# MAGIsDebugger-JLink.net
KiCad netlist of a schematic drawn in Altium Designer
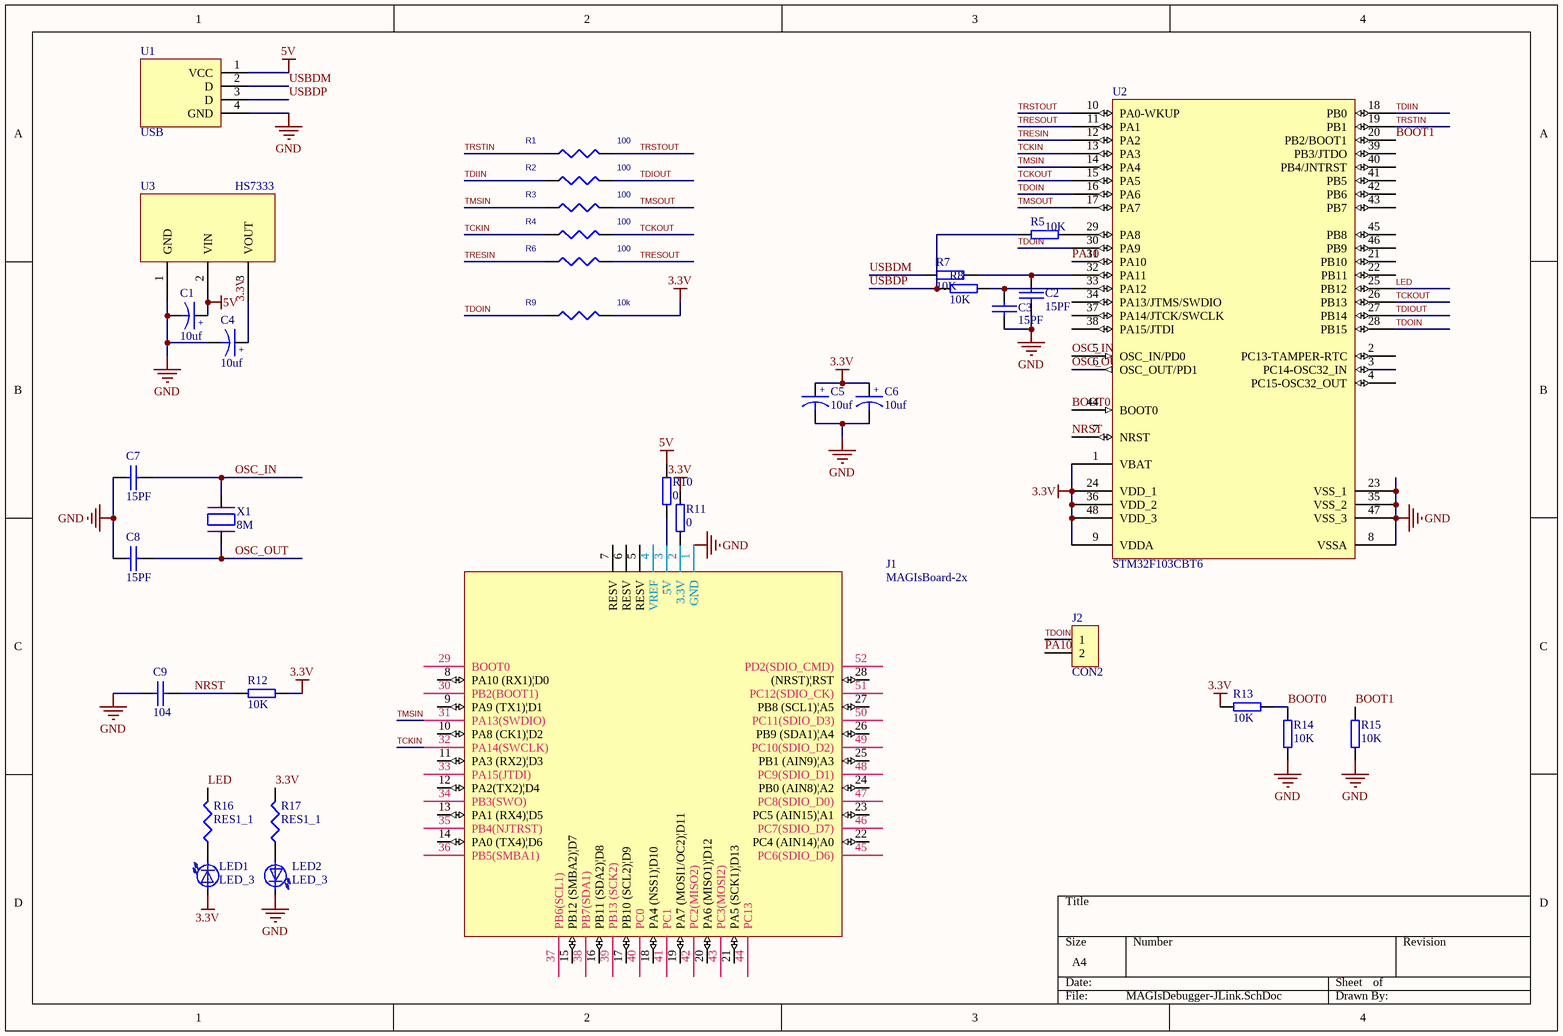
[diagram p0: MAGIsDebugger-JLink.SchDoc]

(export (version "E")
  (design (tool "Eeschema 10.0.6"))
  (components
    (comp (ref "C1")
      (value "10uf")
      (footprint "6-0805_n")
      (description "Capacitor")
      (libsource (lib "电容器") (part "CAPACITOR POL"))
    )
    (comp (ref "C2") (value "15PF") (footprint "6-0805_n") (libsource (lib "STM32") (part "CAP")))
    (comp (ref "C3") (value "15PF") (footprint "6-0805_n") (libsource (lib "STM32") (part "CAP")))
    (comp (ref "C4")
      (value "10uf")
      (footprint "6-0805_n")
      (description "Capacitor")
      (libsource (lib "电容器") (part "CAPACITOR POL"))
    )
    (comp (ref "C5")
      (value "10uf")
      (footprint "6-0805_n")
      (description "Capacitor")
      (libsource (lib "电容器") (part "CAPACITOR POL"))
    )
    (comp (ref "C6")
      (value "10uf")
      (footprint "6-0805_N")
      (description "Capacitor")
      (libsource (lib "电容器") (part "CAPACITOR POL"))
    )
    (comp (ref "C7") (value "15PF") (footprint "6-0805_n") (libsource (lib "STM32") (part "CAP")))
    (comp (ref "C8") (value "15PF") (footprint "6-0805_n") (libsource (lib "STM32") (part "CAP")))
    (comp (ref "C9") (value "104") (footprint "6-0805_n") (libsource (lib "STM32") (part "CAP")))
    (comp (ref "J1")
      (value "MAGIsBoard-2x")
      (footprint "MAGIsBoard-2x")
      (libsource (lib "MAGIsBoard") (part "MAGIsBoard-2x"))
    )
    (comp (ref "J2")
      (value "CON2")
      (footprint "SIP2")
      (description "Connector")
      (libsource (lib "CON系列") (part "CON2"))
    )
    (comp (ref "LED1") (value "LED_3") (footprint "6-0805_n") (libsource (lib "二极管") (part "LED_3")))
    (comp (ref "LED2") (value "LED_3") (footprint "6-0805_n") (libsource (lib "二极管") (part "LED_3")))
    (comp (ref "R1") (value "100") (libsource (lib "*") (part "RESISTOR/SM")))
    (comp (ref "R2") (value "100") (libsource (lib "*") (part "RESISTOR/SM")))
    (comp (ref "R3") (value "100") (libsource (lib "*") (part "RESISTOR/SM")))
    (comp (ref "R4") (value "100") (libsource (lib "*") (part "RESISTOR/SM")))
    (comp (ref "R5") (value "10K") (footprint "6-0805_n") (libsource (lib "STM32") (part "RES")))
    (comp (ref "R6") (value "100") (libsource (lib "*") (part "RESISTOR/SM")))
    (comp (ref "R7") (value "10K") (footprint "6-0805_n") (libsource (lib "STM32") (part "RES")))
    (comp (ref "R8") (value "10K") (footprint "6-0805_n") (libsource (lib "STM32") (part "RES")))
    (comp (ref "R9") (value "10k") (libsource (lib "*") (part "RESISTOR/SM")))
    (comp (ref "R10") (value "0") (footprint "6-0805_n") (libsource (lib "STM32") (part "RES")))
    (comp (ref "R11") (value "0") (footprint "6-0805_n") (libsource (lib "STM32") (part "RES")))
    (comp (ref "R12") (value "10K") (footprint "6-0805_n") (libsource (lib "STM32") (part "RES")))
    (comp (ref "R13") (value "10K") (footprint "6-0805_n") (libsource (lib "STM32") (part "RES")))
    (comp (ref "R14") (value "10K") (footprint "6-0805_n") (libsource (lib "STM32") (part "RES")))
    (comp (ref "R15") (value "10K") (footprint "6-0805_n") (libsource (lib "STM32") (part "RES")))
    (comp (ref "R16") (value "RES1_1") (footprint "6-0805_n") (libsource (lib "电阻器") (part "RES1_1")))
    (comp (ref "R17") (value "RES1_1") (footprint "6-0805_n") (libsource (lib "电阻器") (part "RES1_1")))
    (comp (ref "U1") (value "USB") (footprint "microUSB") (libsource (lib "USB接口") (part "USB")))
    (comp (ref "U2")
      (value "STM32F103CBT6")
      (footprint "LQFP48_N")
      (description "STM32 ARM-based 32-bit MCU with 128 Kbytes Flash, 48-pin LQFP, Industrial Temperature")
      (fields (field (name "PUBLISHER") "Altium Limited"))
      (libsource (lib "ST Microcontroller 32-Bit STM32") (part "STM32F103CBT6"))
    )
    (comp (ref "U3") (value "HS7333") (footprint "HS7333") (libsource (lib "PMIC") (part "HS7333")))
    (comp (ref "X1") (value "8M") (footprint "5032") (libsource (lib "STM32") (part "CRYSTAL")))
  )
  (nets
    (net (code "1") (name "/BOOT0") (class "Default")
      (node (ref "R13") (pin "1") (pinfunction "1_1") (pintype "passive"))
      (node (ref "R14") (pin "2") (pinfunction "2_2") (pintype "passive"))
      (node (ref "U2") (pin "44") (pinfunction "BOOT0_44") (pintype "input"))
    )
    (net (code "2") (name "/BOOT1") (class "Default")
      (node (ref "R15") (pin "2") (pinfunction "2_2") (pintype "passive"))
      (node (ref "U2") (pin "20") (pinfunction "PB2/BOOT1_20") (pintype "bidirectional"))
    )
    (net (code "3") (name "/LED") (class "Default")
      (node (ref "R16") (pin "2") (pinfunction "2_2") (pintype "passive"))
      (node (ref "U2") (pin "25") (pinfunction "PB12_25") (pintype "bidirectional"))
    )
    (net (code "4") (name "/NRST") (class "Default")
      (node (ref "C9") (pin "2") (pinfunction "2_2") (pintype "passive"))
      (node (ref "R12") (pin "1") (pinfunction "1_1") (pintype "passive"))
      (node (ref "U2") (pin "7") (pinfunction "NRST_7") (pintype "bidirectional"))
    )
    (net (code "5") (name "/OSC_IN") (class "Default")
      (node (ref "C7") (pin "2") (pinfunction "2_2") (pintype "passive"))
      (node (ref "U2") (pin "5") (pinfunction "OSC_IN/PD0_5") (pintype "input"))
      (node (ref "X1") (pin "1") (pinfunction "1_1") (pintype "passive"))
    )
    (net (code "6") (name "/OSC_OUT") (class "Default")
      (node (ref "C8") (pin "2") (pinfunction "2_2") (pintype "passive"))
      (node (ref "U2") (pin "6") (pinfunction "OSC_OUT/PD1_6") (pintype "output"))
      (node (ref "X1") (pin "2") (pinfunction "2_2") (pintype "passive"))
    )
    (net (code "7") (name "/PA10") (class "Default")
      (node (ref "J2") (pin "2") (pinfunction "2_2") (pintype "passive"))
      (node (ref "U2") (pin "31") (pinfunction "PA10_31") (pintype "bidirectional"))
    )
    (net (code "8") (name "/TCKIN") (class "Default")
      (node (ref "J1") (pin "32") (pinfunction "PA14(SWCLK)_32") (pintype "passive"))
      (node (ref "R4") (pin "1") (pinfunction "1_1") (pintype "passive"))
      (node (ref "U2") (pin "13") (pinfunction "PA3_13") (pintype "bidirectional"))
    )
    (net (code "9") (name "/TCKOUT") (class "Default")
      (node (ref "R4") (pin "2") (pinfunction "2_2") (pintype "passive"))
      (node (ref "U2") (pin "15") (pinfunction "PA5_15") (pintype "bidirectional"))
      (node (ref "U2") (pin "26") (pinfunction "PB13_26") (pintype "bidirectional"))
    )
    (net (code "10") (name "/TDIIN") (class "Default")
      (node (ref "R2") (pin "1") (pinfunction "1_1") (pintype "passive"))
      (node (ref "U2") (pin "18") (pinfunction "PB0_18") (pintype "bidirectional"))
    )
    (net (code "11") (name "/TDIOUT") (class "Default")
      (node (ref "R2") (pin "2") (pinfunction "2_2") (pintype "passive"))
      (node (ref "U2") (pin "27") (pinfunction "PB14_27") (pintype "bidirectional"))
    )
    (net (code "12") (name "/TDOIN") (class "Default")
      (node (ref "J2") (pin "1") (pinfunction "1_1") (pintype "passive"))
      (node (ref "R9") (pin "1") (pinfunction "1_1") (pintype "passive"))
      (node (ref "U2") (pin "16") (pinfunction "PA6_16") (pintype "bidirectional"))
      (node (ref "U2") (pin "28") (pinfunction "PB15_28") (pintype "bidirectional"))
      (node (ref "U2") (pin "30") (pinfunction "PA9_30") (pintype "bidirectional"))
    )
    (net (code "13") (name "/TMSIN") (class "Default")
      (node (ref "J1") (pin "31") (pinfunction "PA13(SWDIO)_31") (pintype "passive"))
      (node (ref "R3") (pin "1") (pinfunction "1_1") (pintype "passive"))
      (node (ref "U2") (pin "14") (pinfunction "PA4_14") (pintype "bidirectional"))
    )
    (net (code "14") (name "/TMSOUT") (class "Default")
      (node (ref "R3") (pin "2") (pinfunction "2_2") (pintype "passive"))
      (node (ref "U2") (pin "17") (pinfunction "PA7_17") (pintype "bidirectional"))
    )
    (net (code "15") (name "/TRESIN") (class "Default")
      (node (ref "R6") (pin "1") (pinfunction "1_1") (pintype "passive"))
      (node (ref "U2") (pin "12") (pinfunction "PA2_12") (pintype "bidirectional"))
    )
    (net (code "16") (name "/TRESOUT") (class "Default")
      (node (ref "R6") (pin "2") (pinfunction "2_2") (pintype "passive"))
      (node (ref "U2") (pin "11") (pinfunction "PA1_11") (pintype "bidirectional"))
    )
    (net (code "17") (name "/TRSTIN") (class "Default")
      (node (ref "R1") (pin "1") (pinfunction "1_1") (pintype "passive"))
      (node (ref "U2") (pin "19") (pinfunction "PB1_19") (pintype "bidirectional"))
    )
    (net (code "18") (name "/TRSTOUT") (class "Default")
      (node (ref "R1") (pin "2") (pinfunction "2_2") (pintype "passive"))
      (node (ref "U2") (pin "10") (pinfunction "PA0-WKUP_10") (pintype "bidirectional"))
    )
    (net (code "19") (name "/USBDM") (class "Default")
      (node (ref "R7") (pin "1") (pinfunction "1_1") (pintype "passive"))
      (node (ref "U1") (pin "2") (pinfunction "D_2") (pintype "passive"))
    )
    (net (code "20") (name "/USBDP") (class "Default")
      (node (ref "R5") (pin "1") (pinfunction "1_1") (pintype "passive"))
      (node (ref "R8") (pin "1") (pinfunction "1_1") (pintype "passive"))
      (node (ref "U1") (pin "3") (pinfunction "D_3") (pintype "passive"))
    )
    (net (code "21") (name "3.3V") (class "Default")
      (node (ref "C4") (pin "1") (pinfunction "1_1") (pintype "passive"))
      (node (ref "C5") (pin "1") (pinfunction "1_1") (pintype "passive"))
      (node (ref "C6") (pin "1") (pinfunction "1_1") (pintype "passive"))
      (node (ref "LED1") (pin "1") (pinfunction "A_1") (pintype "passive"))
      (node (ref "R11") (pin "1") (pinfunction "1_1") (pintype "passive"))
      (node (ref "R12") (pin "2") (pinfunction "2_2") (pintype "passive"))
      (node (ref "R13") (pin "2") (pinfunction "2_2") (pintype "passive"))
      (node (ref "R17") (pin "2") (pinfunction "2_2") (pintype "passive"))
      (node (ref "R9") (pin "2") (pinfunction "2_2") (pintype "passive"))
      (node (ref "U2") (pin "1") (pinfunction "VBAT_1") (pintype "power_in"))
      (node (ref "U2") (pin "24") (pinfunction "VDD_1_24") (pintype "power_in"))
      (node (ref "U2") (pin "36") (pinfunction "VDD_2_36") (pintype "power_in"))
      (node (ref "U2") (pin "48") (pinfunction "VDD_3_48") (pintype "power_in"))
      (node (ref "U2") (pin "9") (pinfunction "VDDA_9") (pintype "power_in"))
      (node (ref "U3") (pin "3") (pinfunction "VOUT_3") (pintype "passive"))
    )
    (net (code "22") (name "5V") (class "Default")
      (node (ref "C1") (pin "1") (pinfunction "1_1") (pintype "passive"))
      (node (ref "R10") (pin "1") (pinfunction "1_1") (pintype "passive"))
      (node (ref "U1") (pin "1") (pinfunction "VCC_1") (pintype "passive"))
      (node (ref "U3") (pin "2") (pinfunction "VIN_2") (pintype "passive"))
    )
    (net (code "23") (name "GND") (class "Default")
      (node (ref "C1") (pin "2") (pinfunction "2_2") (pintype "passive"))
      (node (ref "C2") (pin "1") (pinfunction "1_1") (pintype "passive"))
      (node (ref "C3") (pin "1") (pinfunction "1_1") (pintype "passive"))
      (node (ref "C4") (pin "2") (pinfunction "2_2") (pintype "passive"))
      (node (ref "C5") (pin "2") (pinfunction "2_2") (pintype "passive"))
      (node (ref "C6") (pin "2") (pinfunction "2_2") (pintype "passive"))
      (node (ref "C7") (pin "1") (pinfunction "1_1") (pintype "passive"))
      (node (ref "C8") (pin "1") (pinfunction "1_1") (pintype "passive"))
      (node (ref "C9") (pin "1") (pinfunction "1_1") (pintype "passive"))
      (node (ref "J1") (pin "1") (pinfunction "GND_1") (pintype "power_in"))
      (node (ref "LED2") (pin "2") (pinfunction "K_2") (pintype "passive"))
      (node (ref "R14") (pin "1") (pinfunction "1_1") (pintype "passive"))
      (node (ref "R15") (pin "1") (pinfunction "1_1") (pintype "passive"))
      (node (ref "U1") (pin "4") (pinfunction "GND_4") (pintype "passive"))
      (node (ref "U2") (pin "23") (pinfunction "VSS_1_23") (pintype "power_in"))
      (node (ref "U2") (pin "35") (pinfunction "VSS_2_35") (pintype "power_in"))
      (node (ref "U2") (pin "47") (pinfunction "VSS_3_47") (pintype "power_in"))
      (node (ref "U2") (pin "8") (pinfunction "VSSA_8") (pintype "power_in"))
      (node (ref "U3") (pin "1") (pinfunction "GND_1") (pintype "passive"))
    )
    (net (code "24") (name "Net-(J1-3.3V)") (class "Default")
      (node (ref "J1") (pin "2") (pinfunction "3.3V_2") (pintype "power_in"))
      (node (ref "R11") (pin "2") (pinfunction "2_2") (pintype "passive"))
    )
    (net (code "25") (name "Net-(J1-5V)") (class "Default")
      (node (ref "J1") (pin "3") (pinfunction "5V_3") (pintype "power_in"))
      (node (ref "R10") (pin "2") (pinfunction "2_2") (pintype "passive"))
    )
    (net (code "26") (name "Net-(LED1-K)") (class "Default")
      (node (ref "LED1") (pin "2") (pinfunction "K_2") (pintype "passive"))
      (node (ref "R16") (pin "1") (pinfunction "1_1") (pintype "passive"))
    )
    (net (code "27") (name "Net-(LED2-A)") (class "Default")
      (node (ref "LED2") (pin "1") (pinfunction "A_1") (pintype "passive"))
      (node (ref "R17") (pin "1") (pinfunction "1_1") (pintype "passive"))
    )
    (net (code "28") (name "Net-(U2-PA8)") (class "Default")
      (node (ref "R5") (pin "2") (pinfunction "2_2") (pintype "passive"))
      (node (ref "U2") (pin "29") (pinfunction "PA8_29") (pintype "bidirectional"))
    )
    (net (code "29") (name "Net-(U2-PA11)") (class "Default")
      (node (ref "C2") (pin "2") (pinfunction "2_2") (pintype "passive"))
      (node (ref "R7") (pin "2") (pinfunction "2_2") (pintype "passive"))
      (node (ref "U2") (pin "32") (pinfunction "PA11_32") (pintype "bidirectional"))
    )
    (net (code "30") (name "Net-(U2-PA12)") (class "Default")
      (node (ref "C3") (pin "2") (pinfunction "2_2") (pintype "passive"))
      (node (ref "R8") (pin "2") (pinfunction "2_2") (pintype "passive"))
      (node (ref "U2") (pin "33") (pinfunction "PA12_33") (pintype "bidirectional"))
    )
    (net (code "31") (name "unconnected-(J1-(NRST)¦RST-Pad28)") (class "Default")
      (node (ref "J1") (pin "28") (pinfunction "(NRST)¦RST_28") (pintype "bidirectional"))
    )
    (net (code "32") (name "unconnected-(J1-BOOT0-Pad29)") (class "Default")
      (node (ref "J1") (pin "29") (pinfunction "BOOT0_29") (pintype "passive"))
    )
    (net (code "33") (name "unconnected-(J1-PA0_(TX4)¦D6-Pad14)") (class "Default")
      (node (ref "J1") (pin "14") (pinfunction "PA0_(TX4)¦D6_14") (pintype "bidirectional"))
    )
    (net (code "34") (name "unconnected-(J1-PA1_(RX4)¦D5-Pad13)") (class "Default")
      (node (ref "J1") (pin "13") (pinfunction "PA1_(RX4)¦D5_13") (pintype "bidirectional"))
    )
    (net (code "35") (name "unconnected-(J1-PA2(TX2)¦D4-Pad12)") (class "Default")
      (node (ref "J1") (pin "12") (pinfunction "PA2(TX2)¦D4_12") (pintype "bidirectional"))
    )
    (net (code "36") (name "unconnected-(J1-PA3_(RX2)¦D3-Pad11)") (class "Default")
      (node (ref "J1") (pin "11") (pinfunction "PA3_(RX2)¦D3_11") (pintype "bidirectional"))
    )
    (net (code "37") (name "unconnected-(J1-PA4_(NSS1)¦D10-Pad18)") (class "Default")
      (node (ref "J1") (pin "18") (pinfunction "PA4_(NSS1)¦D10_18") (pintype "bidirectional"))
    )
    (net (code "38") (name "unconnected-(J1-PA5_(SCK1)¦D13-Pad21)") (class "Default")
      (node (ref "J1") (pin "21") (pinfunction "PA5_(SCK1)¦D13_21") (pintype "bidirectional"))
    )
    (net (code "39") (name "unconnected-(J1-PA6_(MISO1)¦D12-Pad20)") (class "Default")
      (node (ref "J1") (pin "20") (pinfunction "PA6_(MISO1)¦D12_20") (pintype "bidirectional"))
    )
    (net (code "40") (name "unconnected-(J1-PA7_(MOSI1{slash}OC2)¦D11-Pad19)") (class "Default")
      (node (ref "J1") (pin "19") (pinfunction "PA7_(MOSI1/OC2)¦D11_19") (pintype "bidirectional"))
    )
    (net (code "41") (name "unconnected-(J1-PA8_(CK1)¦D2-Pad10)") (class "Default")
      (node (ref "J1") (pin "10") (pinfunction "PA8_(CK1)¦D2_10") (pintype "bidirectional"))
    )
    (net (code "42") (name "unconnected-(J1-PA9_(TX1)¦D1-Pad9)") (class "Default")
      (node (ref "J1") (pin "9") (pinfunction "PA9_(TX1)¦D1_9") (pintype "bidirectional"))
    )
    (net (code "43") (name "unconnected-(J1-PA10_(RX1)¦D0-Pad8)") (class "Default")
      (node (ref "J1") (pin "8") (pinfunction "PA10_(RX1)¦D0_8") (pintype "bidirectional"))
    )
    (net (code "44") (name "unconnected-(J1-PA15(JTDI)-Pad33)") (class "Default")
      (node (ref "J1") (pin "33") (pinfunction "PA15(JTDI)_33") (pintype "passive"))
    )
    (net (code "45") (name "unconnected-(J1-PB0_(AIN8)¦A2-Pad24)") (class "Default")
      (node (ref "J1") (pin "24") (pinfunction "PB0_(AIN8)¦A2_24") (pintype "bidirectional"))
    )
    (net (code "46") (name "unconnected-(J1-PB1_(AIN9)¦A3-Pad25)") (class "Default")
      (node (ref "J1") (pin "25") (pinfunction "PB1_(AIN9)¦A3_25") (pintype "bidirectional"))
    )
    (net (code "47") (name "unconnected-(J1-PB2(BOOT1)-Pad30)") (class "Default")
      (node (ref "J1") (pin "30") (pinfunction "PB2(BOOT1)_30") (pintype "passive"))
    )
    (net (code "48") (name "unconnected-(J1-PB3(SWO)-Pad34)") (class "Default")
      (node (ref "J1") (pin "34") (pinfunction "PB3(SWO)_34") (pintype "passive"))
    )
    (net (code "49") (name "unconnected-(J1-PB4(NJTRST)-Pad35)") (class "Default")
      (node (ref "J1") (pin "35") (pinfunction "PB4(NJTRST)_35") (pintype "passive"))
    )
    (net (code "50") (name "unconnected-(J1-PB5(SMBA1)-Pad36)") (class "Default")
      (node (ref "J1") (pin "36") (pinfunction "PB5(SMBA1)_36") (pintype "passive"))
    )
    (net (code "51") (name "unconnected-(J1-PB6(SCL1)-Pad37)") (class "Default")
      (node (ref "J1") (pin "37") (pinfunction "PB6(SCL1)_37") (pintype "passive"))
    )
    (net (code "52") (name "unconnected-(J1-PB7(SDA1)-Pad38)") (class "Default")
      (node (ref "J1") (pin "38") (pinfunction "PB7(SDA1)_38") (pintype "passive"))
    )
    (net (code "53") (name "unconnected-(J1-PB8_(SCL1)¦A5-Pad27)") (class "Default")
      (node (ref "J1") (pin "27") (pinfunction "PB8_(SCL1)¦A5_27") (pintype "bidirectional"))
    )
    (net (code "54") (name "unconnected-(J1-PB9_(SDA1)¦A4-Pad26)") (class "Default")
      (node (ref "J1") (pin "26") (pinfunction "PB9_(SDA1)¦A4_26") (pintype "bidirectional"))
    )
    (net (code "55") (name "unconnected-(J1-PB10_(SCL2)¦D9-Pad17)") (class "Default")
      (node (ref "J1") (pin "17") (pinfunction "PB10_(SCL2)¦D9_17") (pintype "bidirectional"))
    )
    (net (code "56") (name "unconnected-(J1-PB11_(SDA2)¦D8-Pad16)") (class "Default")
      (node (ref "J1") (pin "16") (pinfunction "PB11_(SDA2)¦D8_16") (pintype "bidirectional"))
    )
    (net (code "57") (name "unconnected-(J1-PB12_(SMBA2)¦D7-Pad15)") (class "Default")
      (node (ref "J1") (pin "15") (pinfunction "PB12_(SMBA2)¦D7_15") (pintype "bidirectional"))
    )
    (net (code "58") (name "unconnected-(J1-PB13_(SCK2)-Pad39)") (class "Default")
      (node (ref "J1") (pin "39") (pinfunction "PB13_(SCK2)_39") (pintype "passive"))
    )
    (net (code "59") (name "unconnected-(J1-PC0-Pad40)") (class "Default")
      (node (ref "J1") (pin "40") (pinfunction "PC0_40") (pintype "passive"))
    )
    (net (code "60") (name "unconnected-(J1-PC1-Pad41)") (class "Default")
      (node (ref "J1") (pin "41") (pinfunction "PC1_41") (pintype "passive"))
    )
    (net (code "61") (name "unconnected-(J1-PC2(MISO2)-Pad42)") (class "Default")
      (node (ref "J1") (pin "42") (pinfunction "PC2(MISO2)_42") (pintype "passive"))
    )
    (net (code "62") (name "unconnected-(J1-PC3(MOSI2)-Pad43)") (class "Default")
      (node (ref "J1") (pin "43") (pinfunction "PC3(MOSI2)_43") (pintype "passive"))
    )
    (net (code "63") (name "unconnected-(J1-PC4_(AIN14)¦A0-Pad22)") (class "Default")
      (node (ref "J1") (pin "22") (pinfunction "PC4_(AIN14)¦A0_22") (pintype "bidirectional"))
    )
    (net (code "64") (name "unconnected-(J1-PC5_(AIN15)¦A1-Pad23)") (class "Default")
      (node (ref "J1") (pin "23") (pinfunction "PC5_(AIN15)¦A1_23") (pintype "bidirectional"))
    )
    (net (code "65") (name "unconnected-(J1-PC6(SDIO_D6)-Pad45)") (class "Default")
      (node (ref "J1") (pin "45") (pinfunction "PC6(SDIO_D6)_45") (pintype "passive"))
    )
    (net (code "66") (name "unconnected-(J1-PC7(SDIO_D7)-Pad46)") (class "Default")
      (node (ref "J1") (pin "46") (pinfunction "PC7(SDIO_D7)_46") (pintype "passive"))
    )
    (net (code "67") (name "unconnected-(J1-PC8(SDIO_D0)-Pad47)") (class "Default")
      (node (ref "J1") (pin "47") (pinfunction "PC8(SDIO_D0)_47") (pintype "passive"))
    )
    (net (code "68") (name "unconnected-(J1-PC9(SDIO_D1)-Pad48)") (class "Default")
      (node (ref "J1") (pin "48") (pinfunction "PC9(SDIO_D1)_48") (pintype "passive"))
    )
    (net (code "69") (name "unconnected-(J1-PC10(SDIO_D2)-Pad49)") (class "Default")
      (node (ref "J1") (pin "49") (pinfunction "PC10(SDIO_D2)_49") (pintype "passive"))
    )
    (net (code "70") (name "unconnected-(J1-PC11(SDIO_D3)-Pad50)") (class "Default")
      (node (ref "J1") (pin "50") (pinfunction "PC11(SDIO_D3)_50") (pintype "passive"))
    )
    (net (code "71") (name "unconnected-(J1-PC12(SDIO_CK)-Pad51)") (class "Default")
      (node (ref "J1") (pin "51") (pinfunction "PC12(SDIO_CK)_51") (pintype "passive"))
    )
    (net (code "72") (name "unconnected-(J1-PC13-Pad44)") (class "Default")
      (node (ref "J1") (pin "44") (pinfunction "PC13_44") (pintype "passive"))
    )
    (net (code "73") (name "unconnected-(J1-PD2(SDIO_CMD)-Pad52)") (class "Default")
      (node (ref "J1") (pin "52") (pinfunction "PD2(SDIO_CMD)_52") (pintype "passive"))
    )
    (net (code "74") (name "unconnected-(J1-RESV-Pad5)") (class "Default")
      (node (ref "J1") (pin "5") (pinfunction "RESV_5") (pintype "passive"))
    )
    (net (code "75") (name "unconnected-(J1-RESV-Pad6)") (class "Default")
      (node (ref "J1") (pin "6") (pinfunction "RESV_6") (pintype "passive"))
    )
    (net (code "76") (name "unconnected-(J1-RESV-Pad7)") (class "Default")
      (node (ref "J1") (pin "7") (pinfunction "RESV_7") (pintype "passive"))
    )
    (net (code "77") (name "unconnected-(J1-VREF-Pad4)") (class "Default")
      (node (ref "J1") (pin "4") (pinfunction "VREF_4") (pintype "passive"))
    )
    (net (code "78") (name "unconnected-(U2-PA13{slash}JTMS{slash}SWDIO-Pad34)") (class "Default")
      (node (ref "U2") (pin "34") (pinfunction "PA13/JTMS/SWDIO_34") (pintype "bidirectional"))
    )
    (net (code "79") (name "unconnected-(U2-PA14{slash}JTCK{slash}SWCLK-Pad37)") (class "Default")
      (node (ref "U2") (pin "37") (pinfunction "PA14/JTCK/SWCLK_37") (pintype "bidirectional"))
    )
    (net (code "80") (name "unconnected-(U2-PA15{slash}JTDI-Pad38)") (class "Default")
      (node (ref "U2") (pin "38") (pinfunction "PA15/JTDI_38") (pintype "bidirectional"))
    )
    (net (code "81") (name "unconnected-(U2-PB3{slash}JTDO-Pad39)") (class "Default")
      (node (ref "U2") (pin "39") (pinfunction "PB3/JTDO_39") (pintype "bidirectional"))
    )
    (net (code "82") (name "unconnected-(U2-PB4{slash}JNTRST-Pad40)") (class "Default")
      (node (ref "U2") (pin "40") (pinfunction "PB4/JNTRST_40") (pintype "bidirectional"))
    )
    (net (code "83") (name "unconnected-(U2-PB5-Pad41)") (class "Default")
      (node (ref "U2") (pin "41") (pinfunction "PB5_41") (pintype "bidirectional"))
    )
    (net (code "84") (name "unconnected-(U2-PB6-Pad42)") (class "Default")
      (node (ref "U2") (pin "42") (pinfunction "PB6_42") (pintype "bidirectional"))
    )
    (net (code "85") (name "unconnected-(U2-PB7-Pad43)") (class "Default")
      (node (ref "U2") (pin "43") (pinfunction "PB7_43") (pintype "bidirectional"))
    )
    (net (code "86") (name "unconnected-(U2-PB8-Pad45)") (class "Default")
      (node (ref "U2") (pin "45") (pinfunction "PB8_45") (pintype "bidirectional"))
    )
    (net (code "87") (name "unconnected-(U2-PB9-Pad46)") (class "Default")
      (node (ref "U2") (pin "46") (pinfunction "PB9_46") (pintype "bidirectional"))
    )
    (net (code "88") (name "unconnected-(U2-PB10-Pad21)") (class "Default")
      (node (ref "U2") (pin "21") (pinfunction "PB10_21") (pintype "bidirectional"))
    )
    (net (code "89") (name "unconnected-(U2-PB11-Pad22)") (class "Default")
      (node (ref "U2") (pin "22") (pinfunction "PB11_22") (pintype "bidirectional"))
    )
    (net (code "90") (name "unconnected-(U2-PC13-TAMPER-RTC-Pad2)") (class "Default")
      (node (ref "U2") (pin "2") (pinfunction "PC13-TAMPER-RTC_2") (pintype "bidirectional"))
    )
    (net (code "91") (name "unconnected-(U2-PC14-OSC32_IN-Pad3)") (class "Default")
      (node (ref "U2") (pin "3") (pinfunction "PC14-OSC32_IN_3") (pintype "bidirectional"))
    )
    (net (code "92") (name "unconnected-(U2-PC15-OSC32_OUT-Pad4)") (class "Default")
      (node (ref "U2") (pin "4") (pinfunction "PC15-OSC32_OUT_4") (pintype "bidirectional"))
    )
  )
)
